# 1_Supply.net
KiCad netlist of a schematic drawn in Altium Designer
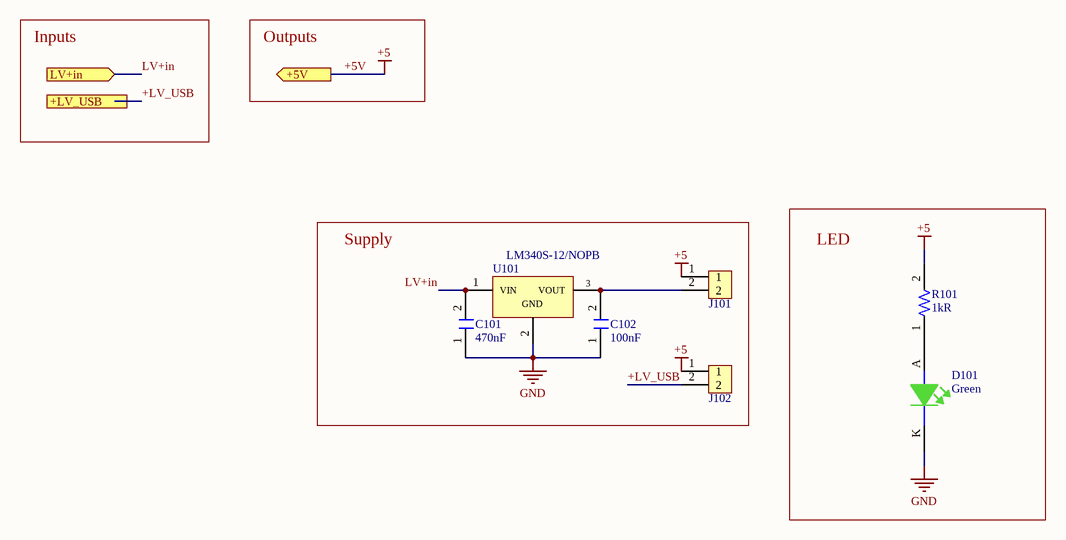
[diagram p0: [1] Supply.SchDoc]

(export (version "E")
  (design (tool "Eeschema 10.0.6"))
  (components
    (comp (ref "C101")
      (value "885012208011")
      (footprint "C1206FNPC-RW")
      (description "Cap, 0.47ΜF, 10V, 10%, X7R, 1206")
      (fields
        (field (name "TOLERANCE") "10%")
        (field (name "CAPACITANCE") "470nF")
        (field (name ".CREATOR") "DO")
      )
      (libsource (lib "Passives") (part "C470n-10V-1206FNPC-X7R"))
    )
    (comp (ref "C102")
      (value "885012208058")
      (footprint "C1206FNPC-RW")
      (description "Cap Cer 0.1UF 25V X7R 1206")
      (fields
        (field (name "MANUFACTURER") "Wurth Electronics")
        (field (name "TOLERANCE") "10%")
        (field (name "CAPACITANCE") "100nF")
        (field (name ".CREATOR") "DO")
      )
      (libsource (lib "Passives") (part "C100n-25V-1206FNPC-X7R"))
    )
    (comp (ref "D101")
      (value "150120GS75000")
      (footprint "LED_1206_WE")
      (description "Led, Green, 520 Nm, 3.2 V, 30 Ma, 450 Mcd Rohs Compliant: Yes")
      (fields
        (field (name "MANUFACTURER") "Wurth Electronics")
        (field (name "COLOR") "Green")
        (field (name ".CREATOR") "GP")
      )
      (libsource (lib "Semiconductor") (part "LEDGS-1206-450"))
    )
    (comp (ref "J101")
      (value "61300211121")
      (footprint "J_Pinheader_1x2")
      (description "CONN HEADER 2 POS 2.54")
      (fields (field (name "MANUFACTURER") "Molex") (field (name ".CREATOR") "GP"))
      (libsource (lib "Electromechanical") (part "J_Jumper"))
    )
    (comp (ref "J102")
      (value "61300211121")
      (footprint "J_Pinheader_1x2")
      (description "CONN HEADER 2 POS 2.54")
      (fields (field (name "MANUFACTURER") "Molex") (field (name ".CREATOR") "GP"))
      (libsource (lib "Electromechanical") (part "J_Jumper"))
    )
    (comp (ref "R101")
      (value "ERJT08J102V")
      (footprint "R1206FTK-W")
      (description "Res Thick Film 1206 1K Ohm 5% 0.33W(1/3W) ±200ppm/C Pad SMD Automotive T/R")
      (fields
        (field (name "MANUFACTURER") "Panasonic")
        (field (name "TOLERANCE") "5%")
        (field (name "RESISTANCE") "1kR")
        (field (name ".CREATOR") "GP")
      )
      (libsource (lib "Passives") (part "R1k-1206FTK"))
    )
    (comp (ref "U101")
      (value "DO_35V-1/12V-TO220")
      (footprint "LDO_35V-1/12V-TO220")
      (description "1.5-A, 35-V, linear voltage regulator 3-TO-220 -40 to 125")
      (fields
        (field (name "MANUFACTURER PART NUMBER") "LM340S-12/NOPB")
        (field (name "MANUFACTURER") "Texas Instruments")
        (field (name "VOLTAGE") "12V")
        (field (name ".CREATOR") "AC")
      )
      (libsource (lib "EMEA- E-Tech Racing- I'Escola d'Enginyeria de Barcelona Est") (part "LDO_35V-1/12V-TO220"))
    )
  )
  (nets
    (net (code "1") (name "+5") (class "Default")
      (node (ref "J101") (pin "1") (pinfunction "1_1") (pintype "passive"))
      (node (ref "J102") (pin "1") (pinfunction "1_1") (pintype "passive"))
      (node (ref "R101") (pin "2") (pinfunction "2_2") (pintype "passive"))
    )
    (net (code "2") (name "/+LV_USB") (class "Default")
      (node (ref "J102") (pin "2") (pinfunction "2_2") (pintype "passive"))
    )
    (net (code "3") (name "/LV+in") (class "Default")
      (node (ref "C101") (pin "2") (pinfunction "2_2") (pintype "passive"))
      (node (ref "U101") (pin "1") (pinfunction "VIN_1") (pintype "passive"))
    )
    (net (code "4") (name "GND") (class "Default")
      (node (ref "C101") (pin "1") (pinfunction "1_1") (pintype "passive"))
      (node (ref "C102") (pin "1") (pinfunction "1_1") (pintype "passive"))
      (node (ref "D101") (pin "K") (pinfunction "K_K") (pintype "passive"))
      (node (ref "U101") (pin "2") (pinfunction "GND_2") (pintype "passive"))
    )
    (net (code "5") (name "Net-(D101-PadA)") (class "Default")
      (node (ref "D101") (pin "A") (pinfunction "A_A") (pintype "passive"))
      (node (ref "R101") (pin "1") (pinfunction "1_1") (pintype "passive"))
    )
    (net (code "6") (name "Net-(U101-VOUT)") (class "Default")
      (node (ref "C102") (pin "2") (pinfunction "2_2") (pintype "passive"))
      (node (ref "J101") (pin "2") (pinfunction "2_2") (pintype "passive"))
      (node (ref "U101") (pin "3") (pinfunction "VOUT_3") (pintype "passive"))
    )
  )
)
